# 7segement2digits1badidea-mk-4_3.net
KiCad netlist of a schematic drawn in EAGLE
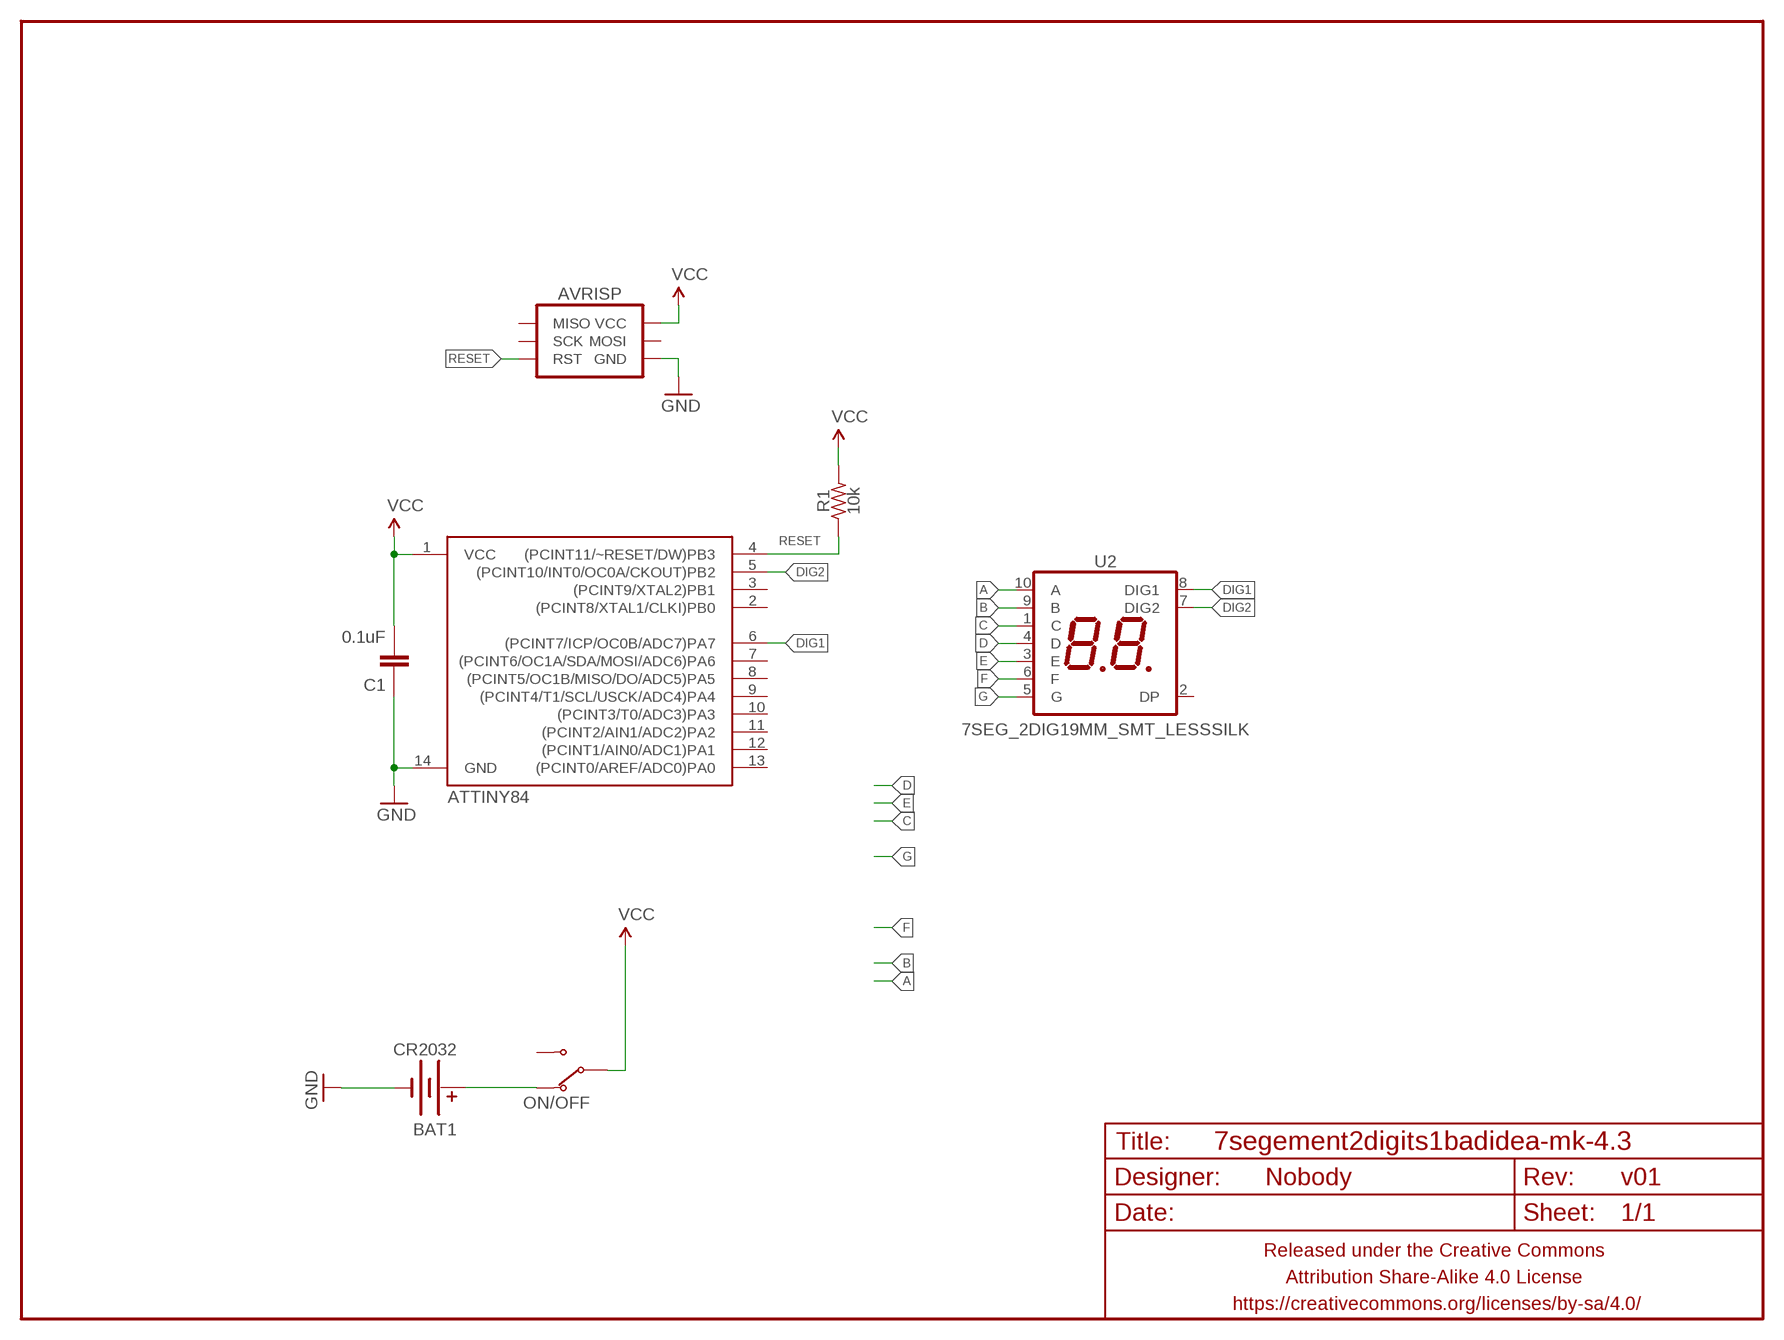
[diagram p0: schematic, sheet 1]

(export (version "E")
  (design (tool "Eeschema 10.0.6"))
  (components
    (comp (ref "AVRISP")
      (value "AVR_SPI_PRG_6AVR-JST-PTH-RA-I2C")
      (footprint "eagle-import:AVR-JST-6-PTH-RA-I2C")
      (libsource (lib "eagle-import") (part "AVR_SPI_PRG_6AVR-JST-PTH-RA-I2C"))
    )
    (comp (ref "BAT1")
      (value "CR2032")
      (footprint "eagle-import:BATTCON_20MM_MINE_STAHPIT")
      (libsource (lib "eagle-import") (part "BATTERY20MM_SMD_TIGHT"))
    )
    (comp (ref "C1")
      (value "0.1uF")
      (footprint "eagle-import:C0805")
      (libsource (lib "eagle-import") (part "CAPACITOR-CERAMICC0805"))
    )
    (comp (ref "FRAME1")
      (value "FRAME-LETTERNO_PACKAGE")
      (footprint "eagle-import:DUMMY")
      (fields (field (name "DESIGNER") "Nobody"))
      (libsource (lib "eagle-import") (part "FRAME-LETTERNO_PACKAGE"))
    )
    (comp (ref "ON/OFF")
      (value "SWITCH-SPDTPTH-RA-2.54MM")
      (footprint "eagle-import:SPDT-RA-2.54MM")
      (libsource (lib "eagle-import") (part "SWITCH-SPDTPTH-RA-2.54MM"))
    )
    (comp (ref "R1")
      (value "10k")
      (footprint "eagle-import:R0805")
      (libsource (lib "eagle-import") (part "RESISTORR0805"))
    )
    (comp (ref "U1")
      (value "ATTINY84")
      (footprint "eagle-import:SO14")
      (libsource (lib "eagle-import") (part "ATTINY84"))
    )
    (comp (ref "U2")
      (value "7SEG_2DIG19MM_SMT_LESSSILK")
      (footprint "eagle-import:7SEG_2DIG_19MM_SMT_LESSSILK")
      (libsource (lib "eagle-import") (part "7SEG_2DIG19MM_SMT_LESSSILK"))
    )
  )
  (nets
    (net (code "1") (name "A") (class "Default")
      (node (ref "U2") (pin "10") (pinfunction "A_10") (pintype "passive"))
    )
    (net (code "2") (name "B") (class "Default")
      (node (ref "U2") (pin "9") (pinfunction "B_9") (pintype "passive"))
    )
    (net (code "3") (name "C") (class "Default")
      (node (ref "U2") (pin "1") (pinfunction "C_1") (pintype "passive"))
    )
    (net (code "4") (name "D") (class "Default")
      (node (ref "U2") (pin "4") (pinfunction "D_4") (pintype "passive"))
    )
    (net (code "5") (name "DIG1") (class "Default")
      (node (ref "U1") (pin "6") (pinfunction "(PCINT7/ICP/OC0B/ADC7)PA7_6") (pintype "bidirectional"))
      (node (ref "U2") (pin "8") (pinfunction "DIG1_8") (pintype "passive"))
    )
    (net (code "6") (name "DIG2") (class "Default")
      (node (ref "U1") (pin "5") (pinfunction "(PCINT10/INT0/OC0A/CKOUT)PB2_5") (pintype "bidirectional"))
      (node (ref "U2") (pin "7") (pinfunction "DIG2_7") (pintype "passive"))
    )
    (net (code "7") (name "E") (class "Default")
      (node (ref "U2") (pin "3") (pinfunction "E_3") (pintype "passive"))
    )
    (net (code "8") (name "F") (class "Default")
      (node (ref "U2") (pin "6") (pinfunction "F_6") (pintype "passive"))
    )
    (net (code "9") (name "G") (class "Default")
      (node (ref "U2") (pin "5") (pinfunction "G_5") (pintype "passive"))
    )
    (net (code "10") (name "GND") (class "Default")
      (node (ref "AVRISP") (pin "GND") (pinfunction "GND_GND") (pintype "passive"))
      (node (ref "BAT1") (pin "BOTTOM") (pinfunction "-_BOTTOM") (pintype "power_in"))
      (node (ref "C1") (pin "1") (pinfunction "1_1") (pintype "passive"))
      (node (ref "U1") (pin "14") (pinfunction "GND_14") (pintype "bidirectional"))
    )
    (net (code "11") (name "Net-(ON/OFF-NC)") (class "Default")
      (node (ref "BAT1") (pin "TOP@1") (pinfunction "+_TOP@1") (pintype "power_in"))
      (node (ref "BAT1") (pin "TOP@2") (pinfunction "+_TOP@2") (pintype "power_in"))
      (node (ref "ON/OFF") (pin "1") (pinfunction "NC_1") (pintype "passive"))
    )
    (net (code "12") (name "RESET") (class "Default")
      (node (ref "AVRISP") (pin "RESET") (pinfunction "RST_RESET") (pintype "passive"))
      (node (ref "R1") (pin "1") (pinfunction "1_1") (pintype "passive"))
      (node (ref "U1") (pin "4") (pinfunction "(PCINT11/~{RESET/DW})PB3_4") (pintype "bidirectional"))
    )
    (net (code "13") (name "VCC") (class "Default")
      (node (ref "AVRISP") (pin "VCC") (pinfunction "VCC_VCC") (pintype "passive"))
      (node (ref "C1") (pin "2") (pinfunction "2_2") (pintype "passive"))
      (node (ref "ON/OFF") (pin "2") (pinfunction "COM_2") (pintype "passive"))
      (node (ref "R1") (pin "2") (pinfunction "2_2") (pintype "passive"))
      (node (ref "U1") (pin "1") (pinfunction "VCC_1") (pintype "bidirectional"))
    )
    (net (code "14") (name "unconnected-(AVRISP-MOSI-PadMOSI{slash}SDA)") (class "Default")
      (node (ref "AVRISP") (pin "MOSI/SDA") (pinfunction "MOSI_MOSI/SDA") (pintype "passive"))
    )
    (net (code "15") (name "unconnected-(AVRISP-PadMISO)") (class "Default")
      (node (ref "AVRISP") (pin "MISO") (pinfunction "MISO_MISO") (pintype "passive"))
    )
    (net (code "16") (name "unconnected-(AVRISP-PadSCK)") (class "Default")
      (node (ref "AVRISP") (pin "SCK") (pinfunction "SCK_SCK") (pintype "passive"))
    )
    (net (code "17") (name "unconnected-(ON/OFF-NO-Pad3)") (class "Default")
      (node (ref "ON/OFF") (pin "3") (pinfunction "NO_3") (pintype "passive"))
    )
    (net (code "18") (name "unconnected-(U1-(PCINT0{slash}AREF{slash}ADC0)PA0-Pad13)") (class "Default")
      (node (ref "U1") (pin "13") (pinfunction "(PCINT0/AREF/ADC0)PA0_13") (pintype "bidirectional"))
    )
    (net (code "19") (name "unconnected-(U1-(PCINT1{slash}AIN0{slash}ADC1)PA1-Pad12)") (class "Default")
      (node (ref "U1") (pin "12") (pinfunction "(PCINT1/AIN0/ADC1)PA1_12") (pintype "bidirectional"))
    )
    (net (code "20") (name "unconnected-(U1-(PCINT2{slash}AIN1{slash}ADC2)PA2-Pad11)") (class "Default")
      (node (ref "U1") (pin "11") (pinfunction "(PCINT2/AIN1/ADC2)PA2_11") (pintype "bidirectional"))
    )
    (net (code "21") (name "unconnected-(U1-(PCINT3{slash}T0{slash}ADC3)PA3-Pad10)") (class "Default")
      (node (ref "U1") (pin "10") (pinfunction "(PCINT3/T0/ADC3)PA3_10") (pintype "bidirectional"))
    )
    (net (code "22") (name "unconnected-(U1-(PCINT4{slash}T1{slash}SCL{slash}USCK{slash}ADC4)PA4-Pad9)") (class "Default")
      (node (ref "U1") (pin "9") (pinfunction "(PCINT4/T1/SCL/USCK/ADC4)PA4_9") (pintype "bidirectional"))
    )
    (net (code "23") (name "unconnected-(U1-(PCINT5{slash}OC1B{slash}MISO{slash}DO{slash}ADC5)PA5-Pad8)") (class "Default")
      (node (ref "U1") (pin "8") (pinfunction "(PCINT5/OC1B/MISO/DO/ADC5)PA5_8") (pintype "bidirectional"))
    )
    (net (code "24") (name "unconnected-(U1-(PCINT6{slash}OC1A{slash}SDA{slash}MOSI{slash}ADC6)PA6-Pad7)") (class "Default")
      (node (ref "U1") (pin "7") (pinfunction "(PCINT6/OC1A/SDA/MOSI/ADC6)PA6_7") (pintype "bidirectional"))
    )
    (net (code "25") (name "unconnected-(U1-(PCINT8{slash}XTAL1{slash}CLKI)PB0-Pad2)") (class "Default")
      (node (ref "U1") (pin "2") (pinfunction "(PCINT8/XTAL1/CLKI)PB0_2") (pintype "bidirectional"))
    )
    (net (code "26") (name "unconnected-(U1-(PCINT9{slash}XTAL2)PB1-Pad3)") (class "Default")
      (node (ref "U1") (pin "3") (pinfunction "(PCINT9/XTAL2)PB1_3") (pintype "bidirectional"))
    )
    (net (code "27") (name "unconnected-(U2-DP-Pad2)") (class "Default")
      (node (ref "U2") (pin "2") (pinfunction "DP_2") (pintype "passive"))
    )
  )
)
